# mjpanel_v2.net
KiCad netlist of a schematic drawn in EAGLE
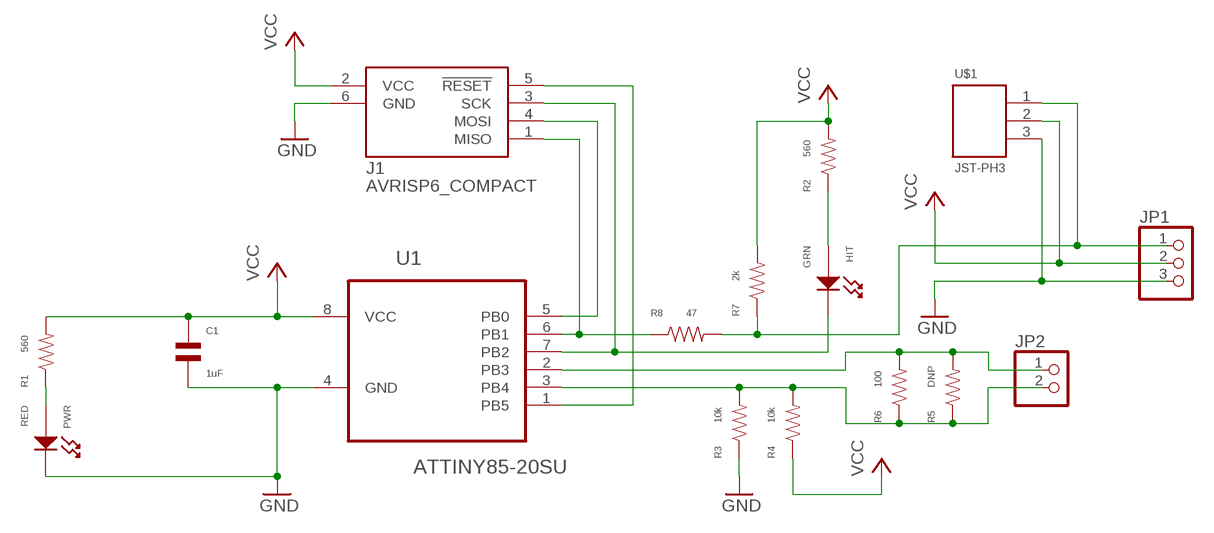
[diagram p0: schematic, sheet 1]

(export (version "E")
  (design (tool "Eeschema 10.0.6"))
  (components
    (comp (ref "C1")
      (value "1uF")
      (footprint "eagle-import:C0603")
      (libsource (lib "eagle-import") (part "CAPACITOR_NP_0603"))
    )
    (comp (ref "HIT")
      (value "GRN")
      (footprint "eagle-import:LED0603")
      (libsource (lib "eagle-import") (part "LED_SINGLE_0603"))
    )
    (comp (ref "J1")
      (value "AVRISP6_COMPACT")
      (footprint "eagle-import:CON6P2R")
      (libsource (lib "eagle-import") (part "AVRISP6_COMPACT"))
    )
    (comp (ref "JP1")
      (value "PINHD-1X3")
      (footprint "eagle-import:1X03")
      (libsource (lib "eagle-import") (part "PINHD-1X3"))
    )
    (comp (ref "JP2")
      (value "PINHD-1X2")
      (footprint "eagle-import:1X02")
      (libsource (lib "eagle-import") (part "PINHD-1X2"))
    )
    (comp (ref "PWR")
      (value "RED")
      (footprint "eagle-import:LED0603")
      (libsource (lib "eagle-import") (part "LED_SINGLE_0603"))
    )
    (comp (ref "R1")
      (value "560")
      (footprint "eagle-import:R0603")
      (libsource (lib "eagle-import") (part "RESISTOR_0603"))
    )
    (comp (ref "R2")
      (value "560")
      (footprint "eagle-import:R0603")
      (libsource (lib "eagle-import") (part "RESISTOR_0603"))
    )
    (comp (ref "R3")
      (value "10k")
      (footprint "eagle-import:R0603")
      (libsource (lib "eagle-import") (part "RESISTOR_0603"))
    )
    (comp (ref "R4")
      (value "10k")
      (footprint "eagle-import:R0603")
      (libsource (lib "eagle-import") (part "RESISTOR_0603"))
    )
    (comp (ref "R5")
      (value "DNP")
      (footprint "eagle-import:R0603")
      (libsource (lib "eagle-import") (part "RESISTOR_0603"))
    )
    (comp (ref "R6")
      (value "100")
      (footprint "eagle-import:R0603")
      (libsource (lib "eagle-import") (part "RESISTOR_0603"))
    )
    (comp (ref "R7")
      (value "2k")
      (footprint "eagle-import:R0603")
      (libsource (lib "eagle-import") (part "RESISTOR_0603"))
    )
    (comp (ref "R8")
      (value "47")
      (footprint "eagle-import:R0603")
      (libsource (lib "eagle-import") (part "RESISTOR_0603"))
    )
    (comp (ref "U$1")
      (value "JST-PH3")
      (footprint "eagle-import:JST-PH3")
      (libsource (lib "eagle-import") (part "JST-PH3"))
    )
    (comp (ref "U1")
      (value "ATTINY85-20SU")
      (footprint "eagle-import:SOIC127P798X216-8N")
      (libsource (lib "eagle-import") (part "ATTINY85-20SU"))
    )
  )
  (nets
    (net (code "1") (name "GND") (class "Default")
      (node (ref "C1") (pin "P$2") (pinfunction "P$2_P$2") (pintype "passive"))
      (node (ref "J1") (pin "6") (pinfunction "GND_6") (pintype "power_in"))
      (node (ref "JP1") (pin "3") (pinfunction "3_3") (pintype "passive"))
      (node (ref "PWR") (pin "CATHODE") (pinfunction "CATHODE_CATHODE") (pintype "power_in"))
      (node (ref "R3") (pin "P$1") (pinfunction "P$1_P$1") (pintype "passive"))
      (node (ref "U$1") (pin "3") (pinfunction "3_3") (pintype "passive"))
      (node (ref "U1") (pin "4") (pinfunction "GND_4") (pintype "passive"))
    )
    (net (code "2") (name "Net-(HIT-PadANODE)") (class "Default")
      (node (ref "HIT") (pin "ANODE") (pinfunction "ANODE_ANODE") (pintype "power_in"))
      (node (ref "R2") (pin "P$1") (pinfunction "P$1_P$1") (pintype "passive"))
    )
    (net (code "3") (name "Net-(J1-MISO)") (class "Default")
      (node (ref "J1") (pin "1") (pinfunction "MISO_1") (pintype "input"))
      (node (ref "R8") (pin "P$1") (pinfunction "P$1_P$1") (pintype "passive"))
      (node (ref "U1") (pin "6") (pinfunction "PB1_6") (pintype "bidirectional"))
    )
    (net (code "4") (name "Net-(J1-MOSI)") (class "Default")
      (node (ref "J1") (pin "4") (pinfunction "MOSI_4") (pintype "output"))
      (node (ref "U1") (pin "5") (pinfunction "PB0_5") (pintype "bidirectional"))
    )
    (net (code "5") (name "Net-(J1-SCK)") (class "Default")
      (node (ref "HIT") (pin "CATHODE") (pinfunction "CATHODE_CATHODE") (pintype "power_in"))
      (node (ref "J1") (pin "3") (pinfunction "SCK_3") (pintype "output"))
      (node (ref "U1") (pin "7") (pinfunction "PB2_7") (pintype "bidirectional"))
    )
    (net (code "6") (name "Net-(J1-~{RESET})") (class "Default")
      (node (ref "J1") (pin "5") (pinfunction "~{RESET}_5") (pintype "output"))
      (node (ref "U1") (pin "1") (pinfunction "PB5_1") (pintype "bidirectional"))
    )
    (net (code "7") (name "Net-(JP1-Pad1)") (class "Default")
      (node (ref "JP1") (pin "1") (pinfunction "1_1") (pintype "passive"))
      (node (ref "R7") (pin "P$1") (pinfunction "P$1_P$1") (pintype "passive"))
      (node (ref "R8") (pin "P$2") (pinfunction "P$2_P$2") (pintype "passive"))
      (node (ref "U$1") (pin "1") (pinfunction "1_1") (pintype "passive"))
    )
    (net (code "8") (name "Net-(PWR-PadANODE)") (class "Default")
      (node (ref "PWR") (pin "ANODE") (pinfunction "ANODE_ANODE") (pintype "power_in"))
      (node (ref "R1") (pin "P$1") (pinfunction "P$1_P$1") (pintype "passive"))
    )
    (net (code "9") (name "Net-(U1-PB3)") (class "Default")
      (node (ref "JP2") (pin "1") (pinfunction "1_1") (pintype "passive"))
      (node (ref "R5") (pin "P$2") (pinfunction "P$2_P$2") (pintype "passive"))
      (node (ref "R6") (pin "P$2") (pinfunction "P$2_P$2") (pintype "passive"))
      (node (ref "U1") (pin "2") (pinfunction "PB3_2") (pintype "bidirectional"))
    )
    (net (code "10") (name "Net-(U1-PB4)") (class "Default")
      (node (ref "JP2") (pin "2") (pinfunction "2_2") (pintype "passive"))
      (node (ref "R3") (pin "P$2") (pinfunction "P$2_P$2") (pintype "passive"))
      (node (ref "R4") (pin "P$2") (pinfunction "P$2_P$2") (pintype "passive"))
      (node (ref "R5") (pin "P$1") (pinfunction "P$1_P$1") (pintype "passive"))
      (node (ref "R6") (pin "P$1") (pinfunction "P$1_P$1") (pintype "passive"))
      (node (ref "U1") (pin "3") (pinfunction "PB4_3") (pintype "bidirectional"))
    )
    (net (code "11") (name "VCC") (class "Default")
      (node (ref "C1") (pin "P$1") (pinfunction "P$1_P$1") (pintype "passive"))
      (node (ref "J1") (pin "2") (pinfunction "VCC_2") (pintype "power_in"))
      (node (ref "JP1") (pin "2") (pinfunction "2_2") (pintype "passive"))
      (node (ref "R1") (pin "P$2") (pinfunction "P$2_P$2") (pintype "passive"))
      (node (ref "R2") (pin "P$2") (pinfunction "P$2_P$2") (pintype "passive"))
      (node (ref "R4") (pin "P$1") (pinfunction "P$1_P$1") (pintype "passive"))
      (node (ref "R7") (pin "P$2") (pinfunction "P$2_P$2") (pintype "passive"))
      (node (ref "U$1") (pin "2") (pinfunction "2_2") (pintype "passive"))
      (node (ref "U1") (pin "8") (pinfunction "VCC_8") (pintype "power_in"))
    )
  )
)
